# 1A18J4_1A20J18_B.net
KiCad netlist of a schematic drawn in Altium Designer
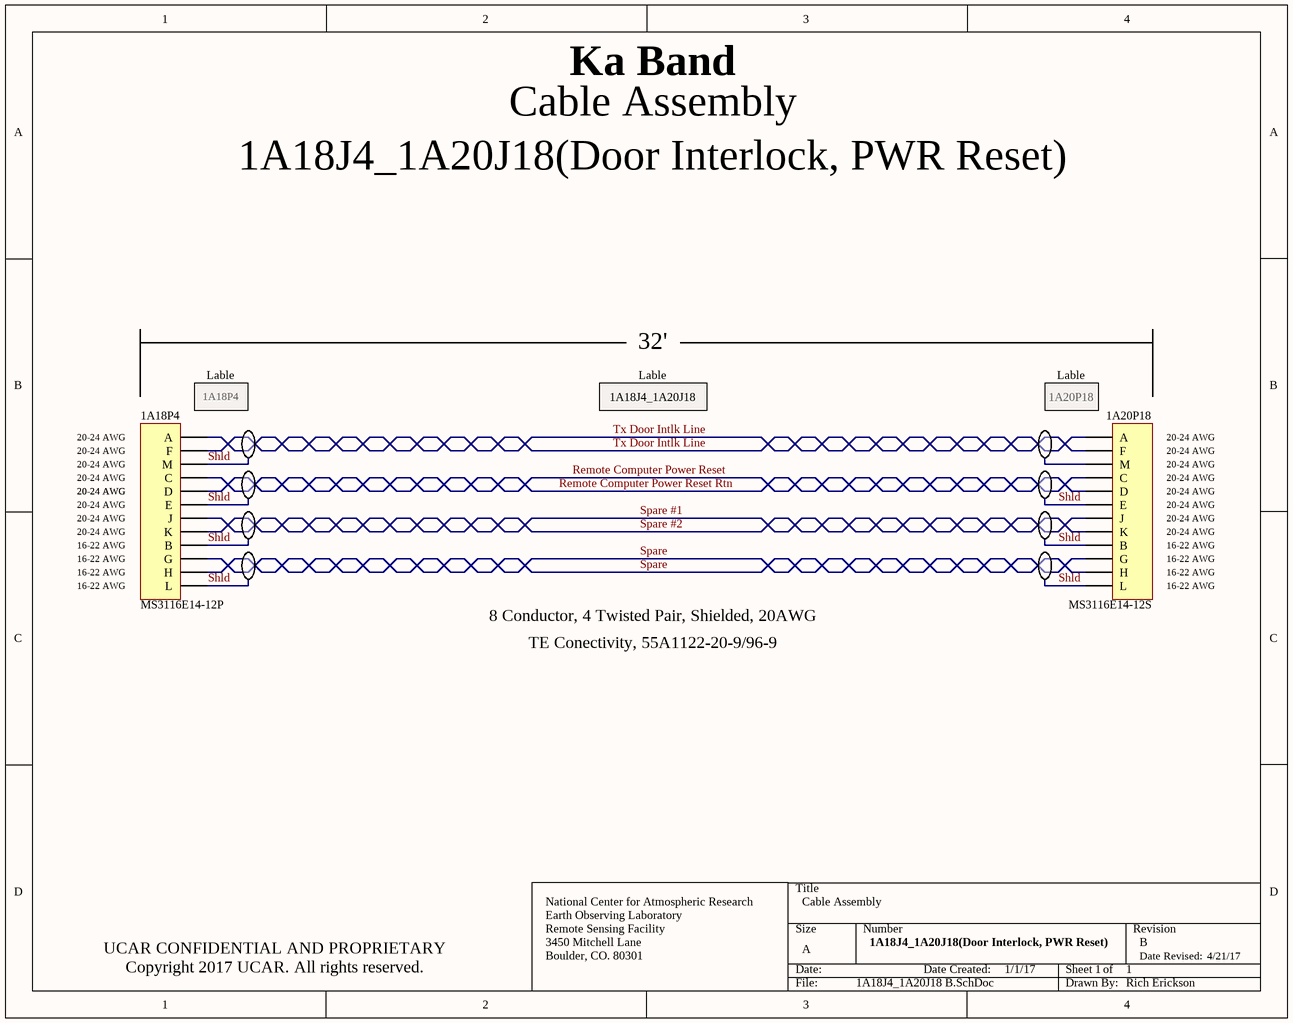
[diagram p0: 1A18J4_1A20J18 B.SchDoc]

(export (version "E")
  (design (tool "Eeschema 10.0.6"))
  (components
    (comp (ref "1A18P4")
      (value "MS3116E14-12P")
      (footprint "HDR1X12")
      (description "Header, 12-Pin")
      (fields (field (name "PUBLISHER") "Altium Limited"))
      (libsource (lib "") (part "Header 12_1"))
    )
    (comp (ref "1A20P18")
      (value "MS3116E14-12S")
      (footprint "HDR1X12")
      (description "Header, 12-Pin")
      (fields (field (name "PUBLISHER") "Altium Limited"))
      (libsource (lib "Miscellaneous Connectors") (part "Header 12"))
    )
  )
  (nets
    (net (code "1") (name "/Remote Computer Power Reset") (class "Default")
      (node (ref "1A18P4") (pin "4") (pinfunction "C_4") (pintype "passive"))
      (node (ref "1A20P18") (pin "4") (pinfunction "C_4") (pintype "passive"))
    )
    (net (code "2") (name "/Remote Computer Power Reset Rtn") (class "Default")
      (node (ref "1A18P4") (pin "5") (pinfunction "D_5") (pintype "passive"))
      (node (ref "1A20P18") (pin "5") (pinfunction "D_5") (pintype "passive"))
    )
    (net (code "3") (name "/Shld") (class "Default")
      (node (ref "1A18P4") (pin "12") (pinfunction "L_12") (pintype "passive"))
      (node (ref "1A18P4") (pin "3") (pinfunction "M_3") (pintype "passive"))
      (node (ref "1A18P4") (pin "6") (pinfunction "E_6") (pintype "passive"))
      (node (ref "1A18P4") (pin "9") (pinfunction "B_9") (pintype "passive"))
      (node (ref "1A20P18") (pin "12") (pinfunction "L_12") (pintype "passive"))
      (node (ref "1A20P18") (pin "6") (pinfunction "E_6") (pintype "passive"))
      (node (ref "1A20P18") (pin "9") (pinfunction "B_9") (pintype "passive"))
    )
    (net (code "4") (name "/Spare") (class "Default")
      (node (ref "1A18P4") (pin "10") (pinfunction "G_10") (pintype "passive"))
      (node (ref "1A18P4") (pin "11") (pinfunction "H_11") (pintype "passive"))
      (node (ref "1A20P18") (pin "10") (pinfunction "G_10") (pintype "passive"))
      (node (ref "1A20P18") (pin "11") (pinfunction "H_11") (pintype "passive"))
    )
    (net (code "5") (name "/Spare #1") (class "Default")
      (node (ref "1A18P4") (pin "7") (pinfunction "J_7") (pintype "passive"))
      (node (ref "1A20P18") (pin "7") (pinfunction "J_7") (pintype "passive"))
    )
    (net (code "6") (name "/Spare #2") (class "Default")
      (node (ref "1A18P4") (pin "8") (pinfunction "K_8") (pintype "passive"))
      (node (ref "1A20P18") (pin "8") (pinfunction "K_8") (pintype "passive"))
    )
    (net (code "7") (name "/Tx Door Intlk Line") (class "Default")
      (node (ref "1A18P4") (pin "1") (pinfunction "A_1") (pintype "passive"))
      (node (ref "1A18P4") (pin "2") (pinfunction "F_2") (pintype "passive"))
      (node (ref "1A20P18") (pin "1") (pinfunction "A_1") (pintype "passive"))
      (node (ref "1A20P18") (pin "2") (pinfunction "F_2") (pintype "passive"))
    )
    (net (code "8") (name "unconnected-(1A20P18-M-Pad3)") (class "Default")
      (node (ref "1A20P18") (pin "3") (pinfunction "M_3") (pintype "passive"))
    )
  )
)
